# LT1171.net
KiCad netlist of a schematic drawn in Altium Designer
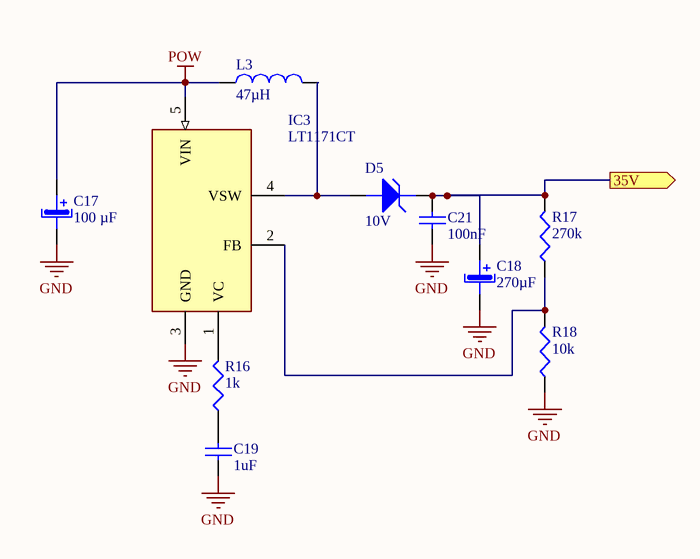
[diagram p0: LT1171.SchDoc]

(export (version "E")
  (design (tool "Eeschema 10.0.6"))
  (components
    (comp (ref "C17")
      (value "100 µF")
      (footprint "CAPP-6x3")
      (description "Condensateur polatisé")
      (fields (field (name "Comment") "Cond pol radial") (field (name "DESIGNER") "ECAM 2004"))
      (libsource (lib "charger_LT3652") (part "Cond pol radial"))
    )
    (comp (ref "C18")
      (value "270µF")
      (footprint "CAPPR2-5x10")
      (description "Condensateur polatisé")
      (fields (field (name "Comment") "Cond pol radial") (field (name "DESIGNER") "ECAM 2004"))
      (libsource (lib "charger_LT3652") (part "Cond pol radial"))
    )
    (comp (ref "C19")
      (value "1uF")
      (footprint "0805 CAP")
      (fields
        (field (name "MANUFACTURER") "Murata")
        (field (name "MANUFACTURER PART NUMBER") "GCM21BR7YA105KA55L")
      )
      (libsource (lib "charger_LT3652") (part "1uF/0805"))
    )
    (comp (ref "C21")
      (value "100nF")
      (footprint "0805 CAP")
      (fields
        (field (name "MANUFACTURER") "Murata")
        (field (name "MANUFACTURER PART NUMBER") "GCM21BR7YA105KA55L")
      )
      (libsource (lib "charger_LT3652") (part "1uF/0805"))
    )
    (comp (ref "D5")
      (value "Diode Zener")
      (footprint "DIODE-0.4")
      (description "Diode Zéner")
      (fields (field (name "VOLTAGE") "10V") (field (name "DESIGNER") "ECAM 2005"))
      (libsource (lib "charger_LT3652") (part "Diode Zener"))
    )
    (comp (ref "IC3")
      (value "LT1171CT")
      (footprint "TO170P457X1022X2306-5P")
      (description "Integrated Circuit")
      (fields
        (field (name "MANUFACTURER_PART_NUMBER") "LT1171CT#PBF")
        (field (name "MOUSER PART NUMBER") "584-LT1171CT#PBF")
      )
      (libsource (lib "charger_LT3652") (part "LT1171CT#PBF"))
    )
    (comp (ref "L3")
      (value "47µH")
      (footprint "Self100uH")
      (description "Inductance")
      (fields (field (name "DESIGNER") "ECAM 2003"))
      (libsource (lib "charger_LT3652") (part "Inductance"))
    )
    (comp (ref "R16")
      (value "1k")
      (footprint "0603 RES")
      (description "Résistance standard")
      (fields (field (name "Comment") "Résistance") (field (name "DESIGNER") "ECAM 2005"))
      (libsource (lib "charger_LT3652") (part "Résistance"))
    )
    (comp (ref "R17")
      (value "270k")
      (footprint "0603 RES")
      (description "Résistance standard")
      (fields (field (name "Comment") "Résistance") (field (name "DESIGNER") "ECAM 2005"))
      (libsource (lib "charger_LT3652") (part "Résistance"))
    )
    (comp (ref "R18")
      (value "10k")
      (footprint "0603 RES")
      (description "Résistance standard")
      (fields (field (name "Comment") "Résistance") (field (name "DESIGNER") "ECAM 2005"))
      (libsource (lib "charger_LT3652") (part "Résistance"))
    )
  )
  (nets
    (net (code "1") (name "/35V") (class "Default")
      (node (ref "C18") (pin "1") (pinfunction "+_1") (pintype "passive"))
      (node (ref "C21") (pin "2") (pinfunction "2_2") (pintype "passive"))
      (node (ref "D5") (pin "2") (pinfunction "K_2") (pintype "passive"))
      (node (ref "R17") (pin "2") (pinfunction "2_2") (pintype "passive"))
    )
    (net (code "2") (name "GND") (class "Default")
      (node (ref "C17") (pin "2") (pinfunction "-_2") (pintype "passive"))
      (node (ref "C18") (pin "2") (pinfunction "-_2") (pintype "passive"))
      (node (ref "C19") (pin "1") (pinfunction "1_1") (pintype "passive"))
      (node (ref "C21") (pin "1") (pinfunction "1_1") (pintype "passive"))
      (node (ref "IC3") (pin "3") (pinfunction "GND_3") (pintype "power_in"))
      (node (ref "R18") (pin "1") (pinfunction "1_1") (pintype "passive"))
    )
    (net (code "3") (name "Net-(C19-Pad2)") (class "Default")
      (node (ref "C19") (pin "2") (pinfunction "2_2") (pintype "passive"))
      (node (ref "R16") (pin "1") (pinfunction "1_1") (pintype "passive"))
    )
    (net (code "4") (name "Net-(D5-A)") (class "Default")
      (node (ref "D5") (pin "1") (pinfunction "A_1") (pintype "passive"))
      (node (ref "IC3") (pin "4") (pinfunction "VSW_4") (pintype "passive"))
      (node (ref "L3") (pin "2") (pinfunction "2_2") (pintype "passive"))
    )
    (net (code "5") (name "Net-(IC3-FB)") (class "Default")
      (node (ref "IC3") (pin "2") (pinfunction "FB_2") (pintype "passive"))
      (node (ref "R17") (pin "1") (pinfunction "1_1") (pintype "passive"))
      (node (ref "R18") (pin "2") (pinfunction "2_2") (pintype "passive"))
    )
    (net (code "6") (name "Net-(IC3-VC)") (class "Default")
      (node (ref "IC3") (pin "1") (pinfunction "VC_1") (pintype "passive"))
      (node (ref "R16") (pin "2") (pinfunction "2_2") (pintype "passive"))
    )
    (net (code "7") (name "POW") (class "Default")
      (node (ref "C17") (pin "1") (pinfunction "+_1") (pintype "passive"))
      (node (ref "IC3") (pin "5") (pinfunction "VIN_5") (pintype "input"))
      (node (ref "L3") (pin "1") (pinfunction "1_1") (pintype "passive"))
    )
  )
)
